# moonclock.net
KiCad netlist of a schematic drawn in EAGLE
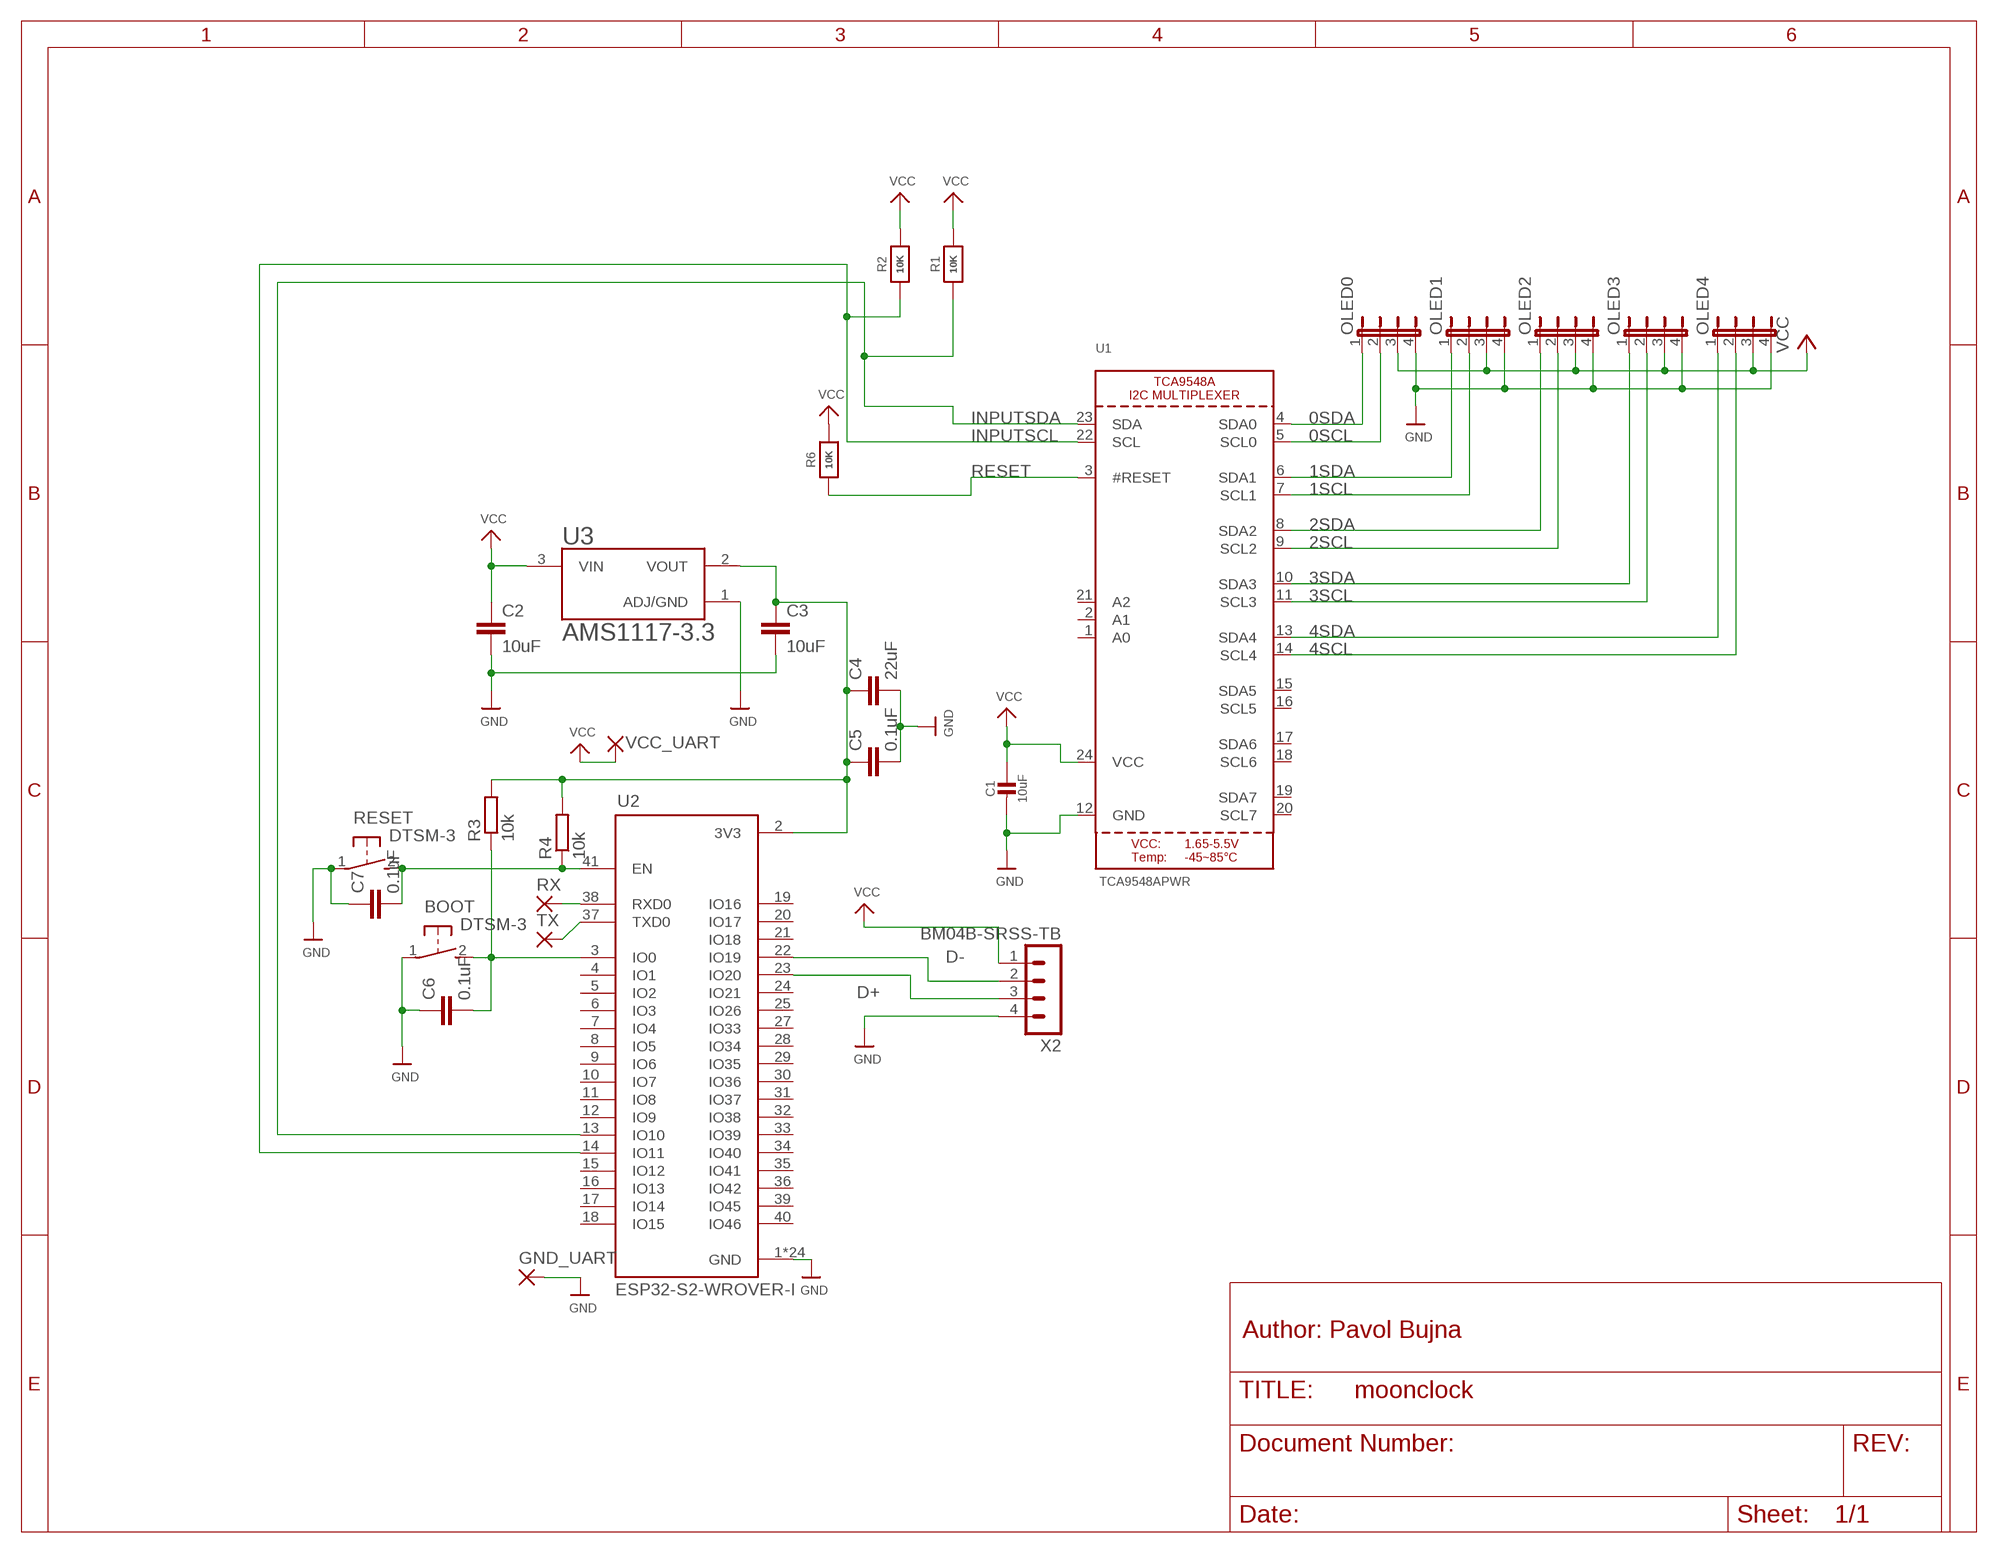
[diagram p0: schematic, sheet 1]

(export (version "E")
  (design (tool "Eeschema 10.0.6"))
  (components
    (comp (ref "BOOT")
      (value "DTSM-3")
      (footprint "eagle-import:DTSM-3")
      (libsource (lib "eagle-import") (part "DTSM-3"))
    )
    (comp (ref "C1")
      (value "10uF")
      (footprint "eagle-import:0805-NO")
      (libsource (lib "eagle-import") (part "CAP_CERAMIC0805-NOOUTLINE"))
    )
    (comp (ref "C2")
      (value "10uF")
      (footprint "eagle-import:C0805")
      (libsource (lib "eagle-import") (part "C-EUC0805"))
    )
    (comp (ref "C3")
      (value "10uF")
      (footprint "eagle-import:C0805")
      (libsource (lib "eagle-import") (part "C-EUC0805"))
    )
    (comp (ref "C4")
      (value "22uF")
      (footprint "eagle-import:C0805")
      (libsource (lib "eagle-import") (part "C-EUC0805"))
    )
    (comp (ref "C5")
      (value "0.1uF")
      (footprint "eagle-import:C0805")
      (libsource (lib "eagle-import") (part "C-EUC0805"))
    )
    (comp (ref "C6")
      (value "0.1uF")
      (footprint "eagle-import:C0805")
      (libsource (lib "eagle-import") (part "C-EUC0805"))
    )
    (comp (ref "C7")
      (value "0.1uF")
      (footprint "eagle-import:C0805")
      (libsource (lib "eagle-import") (part "C-EUC0805"))
    )
    (comp (ref "GND_UART")
      (value "SMD2")
      (footprint "eagle-import:SMD1,27-2,54")
      (libsource (lib "eagle-import") (part "SMD2"))
    )
    (comp (ref "OLED0")
      (value "JP4E")
      (footprint "eagle-import:JP4")
      (libsource (lib "eagle-import") (part "JP4E"))
    )
    (comp (ref "OLED1")
      (value "JP4E")
      (footprint "eagle-import:JP4")
      (libsource (lib "eagle-import") (part "JP4E"))
    )
    (comp (ref "OLED2")
      (value "JP4E")
      (footprint "eagle-import:JP4")
      (libsource (lib "eagle-import") (part "JP4E"))
    )
    (comp (ref "OLED3")
      (value "JP4E")
      (footprint "eagle-import:JP4")
      (libsource (lib "eagle-import") (part "JP4E"))
    )
    (comp (ref "OLED4")
      (value "JP4E")
      (footprint "eagle-import:JP4")
      (libsource (lib "eagle-import") (part "JP4E"))
    )
    (comp (ref "R1")
      (value "10K")
      (footprint "eagle-import:0805-NO")
      (libsource (lib "eagle-import") (part "RESISTOR0805_NOOUTLINE"))
    )
    (comp (ref "R2")
      (value "10K")
      (footprint "eagle-import:0805-NO")
      (libsource (lib "eagle-import") (part "RESISTOR0805_NOOUTLINE"))
    )
    (comp (ref "R3")
      (value "10k")
      (footprint "eagle-import:R0805")
      (libsource (lib "eagle-import") (part "R-EU_R0805"))
    )
    (comp (ref "R4")
      (value "10k")
      (footprint "eagle-import:R0805")
      (libsource (lib "eagle-import") (part "R-EU_R0805"))
    )
    (comp (ref "R6")
      (value "10K")
      (footprint "eagle-import:_0805MP")
      (libsource (lib "eagle-import") (part "RESISTOR_0805MP"))
    )
    (comp (ref "RESET")
      (value "DTSM-3")
      (footprint "eagle-import:DTSM-3")
      (libsource (lib "eagle-import") (part "DTSM-3"))
    )
    (comp (ref "RX")
      (value "SMD2")
      (footprint "eagle-import:SMD1,27-2,54")
      (libsource (lib "eagle-import") (part "SMD2"))
    )
    (comp (ref "TX")
      (value "SMD2")
      (footprint "eagle-import:SMD1,27-2,54")
      (libsource (lib "eagle-import") (part "SMD2"))
    )
    (comp (ref "U1")
      (value "TCA9548APWR")
      (footprint "eagle-import:TSSOP24")
      (libsource (lib "eagle-import") (part "TCA9548A"))
    )
    (comp (ref "U2")
      (value "ESP32-S2-WROVER-I")
      (footprint "eagle-import:ESP32-S2-WROVER-I")
      (libsource (lib "eagle-import") (part "ESP32-S2-WROVER-I"))
    )
    (comp (ref "U3")
      (value "AMS1117-3.3")
      (footprint "eagle-import:SOT229P700X180-4N")
      (fields (field (name "MF") "Advanced Monolithic Systems"))
      (libsource (lib "eagle-import") (part "AMS1117-3.3"))
    )
    (comp (ref "VCC_UART")
      (value "SMD2")
      (footprint "eagle-import:SMD1,27-2,54")
      (libsource (lib "eagle-import") (part "SMD2"))
    )
    (comp (ref "X2")
      (value "BM04B-SRSS-TB")
      (footprint "eagle-import:BM04B-SRSS-TB")
      (libsource (lib "eagle-import") (part "BM04B-SRSS-TB"))
    )
  )
  (nets
    (net (code "1") (name "/0SCL") (class "Default")
      (node (ref "OLED0") (pin "2") (pinfunction "2_2") (pintype "passive"))
      (node (ref "U1") (pin "5") (pinfunction "SCL0_5") (pintype "bidirectional"))
    )
    (net (code "2") (name "/0SDA") (class "Default")
      (node (ref "OLED0") (pin "1") (pinfunction "1_1") (pintype "passive"))
      (node (ref "U1") (pin "4") (pinfunction "SDA0_4") (pintype "bidirectional"))
    )
    (net (code "3") (name "/1SCL") (class "Default")
      (node (ref "OLED1") (pin "2") (pinfunction "2_2") (pintype "passive"))
      (node (ref "U1") (pin "7") (pinfunction "SCL1_7") (pintype "bidirectional"))
    )
    (net (code "4") (name "/1SDA") (class "Default")
      (node (ref "OLED1") (pin "1") (pinfunction "1_1") (pintype "passive"))
      (node (ref "U1") (pin "6") (pinfunction "SDA1_6") (pintype "bidirectional"))
    )
    (net (code "5") (name "/2SCL") (class "Default")
      (node (ref "OLED2") (pin "2") (pinfunction "2_2") (pintype "passive"))
      (node (ref "U1") (pin "9") (pinfunction "SCL2_9") (pintype "bidirectional"))
    )
    (net (code "6") (name "/2SDA") (class "Default")
      (node (ref "OLED2") (pin "1") (pinfunction "1_1") (pintype "passive"))
      (node (ref "U1") (pin "8") (pinfunction "SDA2_8") (pintype "bidirectional"))
    )
    (net (code "7") (name "/3SCL") (class "Default")
      (node (ref "OLED3") (pin "2") (pinfunction "2_2") (pintype "passive"))
      (node (ref "U1") (pin "11") (pinfunction "SCL3_11") (pintype "bidirectional"))
    )
    (net (code "8") (name "/3SDA") (class "Default")
      (node (ref "OLED3") (pin "1") (pinfunction "1_1") (pintype "passive"))
      (node (ref "U1") (pin "10") (pinfunction "SDA3_10") (pintype "bidirectional"))
    )
    (net (code "9") (name "/4SCL") (class "Default")
      (node (ref "OLED4") (pin "2") (pinfunction "2_2") (pintype "passive"))
      (node (ref "U1") (pin "14") (pinfunction "SCL4_14") (pintype "bidirectional"))
    )
    (net (code "10") (name "/4SDA") (class "Default")
      (node (ref "OLED4") (pin "1") (pinfunction "1_1") (pintype "passive"))
      (node (ref "U1") (pin "13") (pinfunction "SDA4_13") (pintype "bidirectional"))
    )
    (net (code "11") (name "/D+") (class "Default")
      (node (ref "U2") (pin "23") (pinfunction "IO20_23") (pintype "bidirectional"))
      (node (ref "X2") (pin "3") (pinfunction "3_3") (pintype "passive"))
    )
    (net (code "12") (name "/D-") (class "Default")
      (node (ref "U2") (pin "22") (pinfunction "IO19_22") (pintype "bidirectional"))
      (node (ref "X2") (pin "2") (pinfunction "2_2") (pintype "passive"))
    )
    (net (code "13") (name "/INPUTSCL") (class "Default")
      (node (ref "R2") (pin "1") (pinfunction "1_1") (pintype "passive"))
      (node (ref "U1") (pin "22") (pinfunction "SCL_22") (pintype "bidirectional"))
      (node (ref "U2") (pin "14") (pinfunction "IO11_14") (pintype "bidirectional"))
    )
    (net (code "14") (name "/INPUTSDA") (class "Default")
      (node (ref "R1") (pin "1") (pinfunction "1_1") (pintype "passive"))
      (node (ref "U1") (pin "23") (pinfunction "SDA_23") (pintype "bidirectional"))
      (node (ref "U2") (pin "13") (pinfunction "IO10_13") (pintype "bidirectional"))
    )
    (net (code "15") (name "/RESET") (class "Default")
      (node (ref "R6") (pin "1") (pinfunction "1_1") (pintype "passive"))
      (node (ref "U1") (pin "3") (pinfunction "#RESET_3") (pintype "bidirectional"))
    )
    (net (code "16") (name "GND") (class "Default")
      (node (ref "BOOT") (pin "1") (pinfunction "1_1") (pintype "passive"))
      (node (ref "C1") (pin "2") (pinfunction "2_2") (pintype "passive"))
      (node (ref "C2") (pin "2") (pinfunction "2_2") (pintype "passive"))
      (node (ref "C3") (pin "2") (pinfunction "2_2") (pintype "passive"))
      (node (ref "C4") (pin "2") (pinfunction "2_2") (pintype "passive"))
      (node (ref "C5") (pin "2") (pinfunction "2_2") (pintype "passive"))
      (node (ref "C6") (pin "1") (pinfunction "1_1") (pintype "passive"))
      (node (ref "C7") (pin "1") (pinfunction "1_1") (pintype "passive"))
      (node (ref "GND_UART") (pin "1") (pinfunction "P_1") (pintype "passive"))
      (node (ref "OLED0") (pin "4") (pinfunction "4_4") (pintype "passive"))
      (node (ref "OLED1") (pin "4") (pinfunction "4_4") (pintype "passive"))
      (node (ref "OLED2") (pin "4") (pinfunction "4_4") (pintype "passive"))
      (node (ref "OLED3") (pin "4") (pinfunction "4_4") (pintype "passive"))
      (node (ref "OLED4") (pin "4") (pinfunction "4_4") (pintype "passive"))
      (node (ref "RESET") (pin "1") (pinfunction "1_1") (pintype "passive"))
      (node (ref "U1") (pin "12") (pinfunction "GND_12") (pintype "bidirectional"))
      (node (ref "U2") (pin "1") (pinfunction "GND_1") (pintype "power_in"))
      (node (ref "U2") (pin "26") (pinfunction "GND_26") (pintype "power_in"))
      (node (ref "U2") (pin "42") (pinfunction "GND_42") (pintype "power_in"))
      (node (ref "U2") (pin "43.1") (pinfunction "GND_43.1") (pintype "power_in"))
      (node (ref "U2") (pin "43.10") (pinfunction "GND_43.10") (pintype "power_in"))
      (node (ref "U2") (pin "43.11") (pinfunction "GND_43.11") (pintype "power_in"))
      (node (ref "U2") (pin "43.12") (pinfunction "GND_43.12") (pintype "power_in"))
      (node (ref "U2") (pin "43.13") (pinfunction "GND_43.13") (pintype "power_in"))
      (node (ref "U2") (pin "43.14") (pinfunction "GND_43.14") (pintype "power_in"))
      (node (ref "U2") (pin "43.15") (pinfunction "GND_43.15") (pintype "power_in"))
      (node (ref "U2") (pin "43.16") (pinfunction "GND_43.16") (pintype "power_in"))
      (node (ref "U2") (pin "43.17") (pinfunction "GND_43.17") (pintype "power_in"))
      (node (ref "U2") (pin "43.18") (pinfunction "GND_43.18") (pintype "power_in"))
      (node (ref "U2") (pin "43.19") (pinfunction "GND_43.19") (pintype "power_in"))
      (node (ref "U2") (pin "43.2") (pinfunction "GND_43.2") (pintype "power_in"))
      (node (ref "U2") (pin "43.20") (pinfunction "GND_43.20") (pintype "power_in"))
      (node (ref "U2") (pin "43.21") (pinfunction "GND_43.21") (pintype "power_in"))
      (node (ref "U2") (pin "43.3") (pinfunction "GND_43.3") (pintype "power_in"))
      (node (ref "U2") (pin "43.4") (pinfunction "GND_43.4") (pintype "power_in"))
      (node (ref "U2") (pin "43.5") (pinfunction "GND_43.5") (pintype "power_in"))
      (node (ref "U2") (pin "43.6") (pinfunction "GND_43.6") (pintype "power_in"))
      (node (ref "U2") (pin "43.7") (pinfunction "GND_43.7") (pintype "power_in"))
      (node (ref "U2") (pin "43.8") (pinfunction "GND_43.8") (pintype "power_in"))
      (node (ref "U2") (pin "43.9") (pinfunction "GND_43.9") (pintype "power_in"))
      (node (ref "U3") (pin "1") (pinfunction "ADJ/GND_1") (pintype "power_in"))
      (node (ref "X2") (pin "4") (pinfunction "4_4") (pintype "passive"))
    )
    (net (code "17") (name "Net-(RX-P)") (class "Default")
      (node (ref "RX") (pin "1") (pinfunction "P_1") (pintype "passive"))
      (node (ref "U2") (pin "38") (pinfunction "RXD0_38") (pintype "bidirectional"))
    )
    (net (code "18") (name "Net-(TX-P)") (class "Default")
      (node (ref "TX") (pin "1") (pinfunction "P_1") (pintype "passive"))
      (node (ref "U2") (pin "37") (pinfunction "TXD0_37") (pintype "bidirectional"))
    )
    (net (code "19") (name "Net-(U2-3V3)") (class "Default")
      (node (ref "C3") (pin "1") (pinfunction "1_1") (pintype "passive"))
      (node (ref "C4") (pin "1") (pinfunction "1_1") (pintype "passive"))
      (node (ref "C5") (pin "1") (pinfunction "1_1") (pintype "passive"))
      (node (ref "R3") (pin "2") (pinfunction "2_2") (pintype "passive"))
      (node (ref "R4") (pin "2") (pinfunction "2_2") (pintype "passive"))
      (node (ref "U2") (pin "2") (pinfunction "3V3_2") (pintype "power_in"))
      (node (ref "U3") (pin "2") (pinfunction "VOUT_2") (pintype "output"))
    )
    (net (code "20") (name "Net-(U2-EN)") (class "Default")
      (node (ref "C7") (pin "2") (pinfunction "2_2") (pintype "passive"))
      (node (ref "R4") (pin "1") (pinfunction "1_1") (pintype "passive"))
      (node (ref "RESET") (pin "2") (pinfunction "2_2") (pintype "passive"))
      (node (ref "U2") (pin "41") (pinfunction "EN_41") (pintype "input"))
    )
    (net (code "21") (name "Net-(U2-IO0)") (class "Default")
      (node (ref "BOOT") (pin "2") (pinfunction "2_2") (pintype "passive"))
      (node (ref "C6") (pin "2") (pinfunction "2_2") (pintype "passive"))
      (node (ref "R3") (pin "1") (pinfunction "1_1") (pintype "passive"))
      (node (ref "U2") (pin "3") (pinfunction "IO0_3") (pintype "bidirectional"))
    )
    (net (code "22") (name "VCC") (class "Default")
      (node (ref "C1") (pin "1") (pinfunction "1_1") (pintype "passive"))
      (node (ref "C2") (pin "1") (pinfunction "1_1") (pintype "passive"))
      (node (ref "OLED0") (pin "3") (pinfunction "3_3") (pintype "passive"))
      (node (ref "OLED1") (pin "3") (pinfunction "3_3") (pintype "passive"))
      (node (ref "OLED2") (pin "3") (pinfunction "3_3") (pintype "passive"))
      (node (ref "OLED3") (pin "3") (pinfunction "3_3") (pintype "passive"))
      (node (ref "OLED4") (pin "3") (pinfunction "3_3") (pintype "passive"))
      (node (ref "R1") (pin "2") (pinfunction "2_2") (pintype "passive"))
      (node (ref "R2") (pin "2") (pinfunction "2_2") (pintype "passive"))
      (node (ref "R6") (pin "2") (pinfunction "2_2") (pintype "passive"))
      (node (ref "U1") (pin "24") (pinfunction "VCC_24") (pintype "bidirectional"))
      (node (ref "U3") (pin "3") (pinfunction "VIN_3") (pintype "input"))
      (node (ref "VCC_UART") (pin "1") (pinfunction "P_1") (pintype "passive"))
      (node (ref "X2") (pin "1") (pinfunction "1_1") (pintype "passive"))
    )
    (net (code "23") (name "unconnected-(U1-A0-Pad1)") (class "Default")
      (node (ref "U1") (pin "1") (pinfunction "A0_1") (pintype "bidirectional"))
    )
    (net (code "24") (name "unconnected-(U1-A1-Pad2)") (class "Default")
      (node (ref "U1") (pin "2") (pinfunction "A1_2") (pintype "bidirectional"))
    )
    (net (code "25") (name "unconnected-(U1-A2-Pad21)") (class "Default")
      (node (ref "U1") (pin "21") (pinfunction "A2_21") (pintype "bidirectional"))
    )
    (net (code "26") (name "unconnected-(U1-SCL5-Pad16)") (class "Default")
      (node (ref "U1") (pin "16") (pinfunction "SCL5_16") (pintype "bidirectional"))
    )
    (net (code "27") (name "unconnected-(U1-SCL6-Pad18)") (class "Default")
      (node (ref "U1") (pin "18") (pinfunction "SCL6_18") (pintype "bidirectional"))
    )
    (net (code "28") (name "unconnected-(U1-SCL7-Pad20)") (class "Default")
      (node (ref "U1") (pin "20") (pinfunction "SCL7_20") (pintype "bidirectional"))
    )
    (net (code "29") (name "unconnected-(U1-SDA5-Pad15)") (class "Default")
      (node (ref "U1") (pin "15") (pinfunction "SDA5_15") (pintype "bidirectional"))
    )
    (net (code "30") (name "unconnected-(U1-SDA6-Pad17)") (class "Default")
      (node (ref "U1") (pin "17") (pinfunction "SDA6_17") (pintype "bidirectional"))
    )
    (net (code "31") (name "unconnected-(U1-SDA7-Pad19)") (class "Default")
      (node (ref "U1") (pin "19") (pinfunction "SDA7_19") (pintype "bidirectional"))
    )
    (net (code "32") (name "unconnected-(U2-IO1-Pad4)") (class "Default")
      (node (ref "U2") (pin "4") (pinfunction "IO1_4") (pintype "bidirectional"))
    )
    (net (code "33") (name "unconnected-(U2-IO2-Pad5)") (class "Default")
      (node (ref "U2") (pin "5") (pinfunction "IO2_5") (pintype "bidirectional"))
    )
    (net (code "34") (name "unconnected-(U2-IO3-Pad6)") (class "Default")
      (node (ref "U2") (pin "6") (pinfunction "IO3_6") (pintype "bidirectional"))
    )
    (net (code "35") (name "unconnected-(U2-IO4-Pad7)") (class "Default")
      (node (ref "U2") (pin "7") (pinfunction "IO4_7") (pintype "bidirectional"))
    )
    (net (code "36") (name "unconnected-(U2-IO5-Pad8)") (class "Default")
      (node (ref "U2") (pin "8") (pinfunction "IO5_8") (pintype "bidirectional"))
    )
    (net (code "37") (name "unconnected-(U2-IO6-Pad9)") (class "Default")
      (node (ref "U2") (pin "9") (pinfunction "IO6_9") (pintype "bidirectional"))
    )
    (net (code "38") (name "unconnected-(U2-IO7-Pad10)") (class "Default")
      (node (ref "U2") (pin "10") (pinfunction "IO7_10") (pintype "bidirectional"))
    )
    (net (code "39") (name "unconnected-(U2-IO8-Pad11)") (class "Default")
      (node (ref "U2") (pin "11") (pinfunction "IO8_11") (pintype "bidirectional"))
    )
    (net (code "40") (name "unconnected-(U2-IO9-Pad12)") (class "Default")
      (node (ref "U2") (pin "12") (pinfunction "IO9_12") (pintype "bidirectional"))
    )
    (net (code "41") (name "unconnected-(U2-IO12-Pad15)") (class "Default")
      (node (ref "U2") (pin "15") (pinfunction "IO12_15") (pintype "bidirectional"))
    )
    (net (code "42") (name "unconnected-(U2-IO13-Pad16)") (class "Default")
      (node (ref "U2") (pin "16") (pinfunction "IO13_16") (pintype "bidirectional"))
    )
    (net (code "43") (name "unconnected-(U2-IO14-Pad17)") (class "Default")
      (node (ref "U2") (pin "17") (pinfunction "IO14_17") (pintype "bidirectional"))
    )
    (net (code "44") (name "unconnected-(U2-IO15-Pad18)") (class "Default")
      (node (ref "U2") (pin "18") (pinfunction "IO15_18") (pintype "bidirectional"))
    )
    (net (code "45") (name "unconnected-(U2-IO16-Pad19)") (class "Default")
      (node (ref "U2") (pin "19") (pinfunction "IO16_19") (pintype "bidirectional"))
    )
    (net (code "46") (name "unconnected-(U2-IO17-Pad20)") (class "Default")
      (node (ref "U2") (pin "20") (pinfunction "IO17_20") (pintype "bidirectional"))
    )
    (net (code "47") (name "unconnected-(U2-IO18-Pad21)") (class "Default")
      (node (ref "U2") (pin "21") (pinfunction "IO18_21") (pintype "bidirectional"))
    )
    (net (code "48") (name "unconnected-(U2-IO21-Pad24)") (class "Default")
      (node (ref "U2") (pin "24") (pinfunction "IO21_24") (pintype "bidirectional"))
    )
    (net (code "49") (name "unconnected-(U2-IO26-Pad25)") (class "Default")
      (node (ref "U2") (pin "25") (pinfunction "IO26_25") (pintype "bidirectional"))
    )
    (net (code "50") (name "unconnected-(U2-IO33-Pad27)") (class "Default")
      (node (ref "U2") (pin "27") (pinfunction "IO33_27") (pintype "bidirectional"))
    )
    (net (code "51") (name "unconnected-(U2-IO34-Pad28)") (class "Default")
      (node (ref "U2") (pin "28") (pinfunction "IO34_28") (pintype "bidirectional"))
    )
    (net (code "52") (name "unconnected-(U2-IO35-Pad29)") (class "Default")
      (node (ref "U2") (pin "29") (pinfunction "IO35_29") (pintype "bidirectional"))
    )
    (net (code "53") (name "unconnected-(U2-IO36-Pad30)") (class "Default")
      (node (ref "U2") (pin "30") (pinfunction "IO36_30") (pintype "bidirectional"))
    )
    (net (code "54") (name "unconnected-(U2-IO37-Pad31)") (class "Default")
      (node (ref "U2") (pin "31") (pinfunction "IO37_31") (pintype "bidirectional"))
    )
    (net (code "55") (name "unconnected-(U2-IO38-Pad32)") (class "Default")
      (node (ref "U2") (pin "32") (pinfunction "IO38_32") (pintype "bidirectional"))
    )
    (net (code "56") (name "unconnected-(U2-IO39-Pad33)") (class "Default")
      (node (ref "U2") (pin "33") (pinfunction "IO39_33") (pintype "bidirectional"))
    )
    (net (code "57") (name "unconnected-(U2-IO40-Pad34)") (class "Default")
      (node (ref "U2") (pin "34") (pinfunction "IO40_34") (pintype "bidirectional"))
    )
    (net (code "58") (name "unconnected-(U2-IO41-Pad35)") (class "Default")
      (node (ref "U2") (pin "35") (pinfunction "IO41_35") (pintype "bidirectional"))
    )
    (net (code "59") (name "unconnected-(U2-IO42-Pad36)") (class "Default")
      (node (ref "U2") (pin "36") (pinfunction "IO42_36") (pintype "bidirectional"))
    )
    (net (code "60") (name "unconnected-(U2-IO45-Pad39)") (class "Default")
      (node (ref "U2") (pin "39") (pinfunction "IO45_39") (pintype "bidirectional"))
    )
    (net (code "61") (name "unconnected-(U2-IO46-Pad40)") (class "Default")
      (node (ref "U2") (pin "40") (pinfunction "IO46_40") (pintype "bidirectional"))
    )
  )
)
